# AAA_PowerSupply.net
KiCad netlist of a schematic drawn in EAGLE
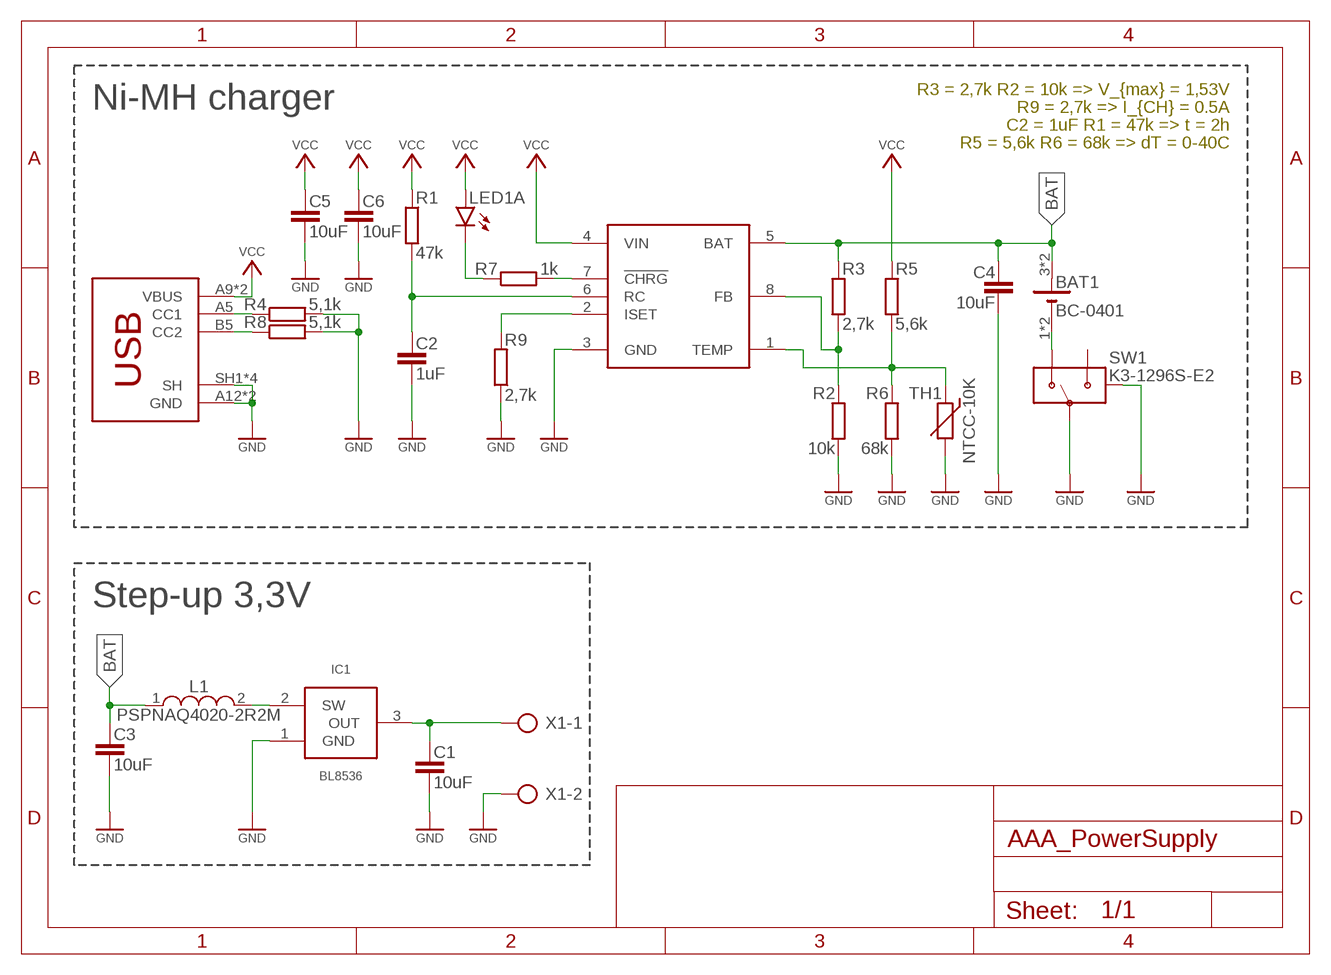
[diagram p0: schematic, sheet 1]

(export (version "E")
  (design (tool "Eeschema 10.0.6"))
  (components
    (comp (ref "BAT1")
      (value "BC-0401")
      (footprint "eagle-import:BC-0401")
      (libsource (lib "eagle-import") (part "BC-0401"))
    )
    (comp (ref "C1")
      (value "10uF")
      (footprint "eagle-import:C0805")
      (fields (field (name "SPICEPREFIX") "C"))
      (libsource (lib "eagle-import") (part "C-EUC0805"))
    )
    (comp (ref "C2")
      (value "1uF")
      (footprint "eagle-import:C0805")
      (fields (field (name "SPICEPREFIX") "C"))
      (libsource (lib "eagle-import") (part "C-EUC0805"))
    )
    (comp (ref "C3")
      (value "10uF")
      (footprint "eagle-import:C0805")
      (fields (field (name "SPICEPREFIX") "C"))
      (libsource (lib "eagle-import") (part "C-EUC0805"))
    )
    (comp (ref "C4")
      (value "10uF")
      (footprint "eagle-import:C0805")
      (fields (field (name "SPICEPREFIX") "C"))
      (libsource (lib "eagle-import") (part "C-EUC0805"))
    )
    (comp (ref "C5")
      (value "10uF")
      (footprint "eagle-import:C0805")
      (fields (field (name "SPICEPREFIX") "C"))
      (libsource (lib "eagle-import") (part "C-EUC0805"))
    )
    (comp (ref "C6")
      (value "10uF")
      (footprint "eagle-import:C0805")
      (fields (field (name "SPICEPREFIX") "C"))
      (libsource (lib "eagle-import") (part "C-EUC0805"))
    )
    (comp (ref "IC1")
      (value "BL8536")
      (footprint "eagle-import:SOT23")
      (libsource (lib "eagle-import") (part "BL8536"))
    )
    (comp (ref "IC2")
      (value "CN3085")
      (footprint "eagle-import:SOP8_THERMAL")
      (libsource (lib "eagle-import") (part "CN3085"))
    )
    (comp (ref "L1")
      (value "PSPNAQ4020-2R2M")
      (footprint "eagle-import:L-4X4")
      (libsource (lib "eagle-import") (part "INDUCTOR-4X4"))
    )
    (comp (ref "LED1")
      (value "LSG-T676")
      (footprint "eagle-import:WL-SFCW-0603")
      (libsource (lib "eagle-import") (part "LSG-T676"))
    )
    (comp (ref "R1")
      (value "47k")
      (footprint "eagle-import:R0805")
      (libsource (lib "eagle-import") (part "R-EU_R0805"))
    )
    (comp (ref "R2")
      (value "10k")
      (footprint "eagle-import:R0805")
      (libsource (lib "eagle-import") (part "R-EU_R0805"))
    )
    (comp (ref "R3")
      (value "2,7k")
      (footprint "eagle-import:R0805")
      (libsource (lib "eagle-import") (part "R-EU_R0805"))
    )
    (comp (ref "R4")
      (value "5,1k")
      (footprint "eagle-import:R0805")
      (libsource (lib "eagle-import") (part "R-EU_R0805"))
    )
    (comp (ref "R5")
      (value "5,6k")
      (footprint "eagle-import:R0805")
      (libsource (lib "eagle-import") (part "R-EU_R0805"))
    )
    (comp (ref "R6")
      (value "68k")
      (footprint "eagle-import:R0805")
      (libsource (lib "eagle-import") (part "R-EU_R0805"))
    )
    (comp (ref "R7")
      (value "1k")
      (footprint "eagle-import:R0805")
      (libsource (lib "eagle-import") (part "R-EU_R0805"))
    )
    (comp (ref "R8")
      (value "5,1k")
      (footprint "eagle-import:R0805")
      (libsource (lib "eagle-import") (part "R-EU_R0805"))
    )
    (comp (ref "R9")
      (value "2,7k")
      (footprint "eagle-import:R0805")
      (libsource (lib "eagle-import") (part "R-EU_R0805"))
    )
    (comp (ref "SW1")
      (value "K3-1296S-E2")
      (footprint "eagle-import:K3-1296S-E2")
      (libsource (lib "eagle-import") (part "K3-1296S-E2"))
    )
    (comp (ref "TH1")
      (value "NTCC-10K")
      (footprint "eagle-import:RS-2,5")
      (libsource (lib "eagle-import") (part "THERMISTOR-2,5"))
    )
    (comp (ref "X1")
      (value "AK500/2")
      (footprint "eagle-import:AK500_2")
      (libsource (lib "eagle-import") (part "AK500/2"))
    )
    (comp (ref "X2")
      (value "HC-TYPE-C-6P-01QT")
      (footprint "eagle-import:HC-TYPE-C-6P-01QT")
      (libsource (lib "eagle-import") (part "HC-TYPE-C-6P-01QT"))
    )
  )
  (nets
    (net (code "1") (name "BAT") (class "Default")
      (node (ref "BAT1") (pin "3") (pinfunction "+_3") (pintype "passive"))
      (node (ref "BAT1") (pin "4") (pinfunction "+_4") (pintype "passive"))
      (node (ref "C3") (pin "1") (pinfunction "1_1") (pintype "passive"))
      (node (ref "C4") (pin "1") (pinfunction "1_1") (pintype "passive"))
      (node (ref "IC2") (pin "5") (pinfunction "BAT_5") (pintype "bidirectional"))
      (node (ref "L1") (pin "1") (pinfunction "1_1") (pintype "passive"))
      (node (ref "R3") (pin "1") (pinfunction "1_1") (pintype "passive"))
    )
    (net (code "2") (name "GND") (class "Default")
      (node (ref "C1") (pin "2") (pinfunction "2_2") (pintype "passive"))
      (node (ref "C2") (pin "2") (pinfunction "2_2") (pintype "passive"))
      (node (ref "C3") (pin "2") (pinfunction "2_2") (pintype "passive"))
      (node (ref "C4") (pin "2") (pinfunction "2_2") (pintype "passive"))
      (node (ref "C5") (pin "2") (pinfunction "2_2") (pintype "passive"))
      (node (ref "C6") (pin "2") (pinfunction "2_2") (pintype "passive"))
      (node (ref "IC1") (pin "1") (pinfunction "GND_1") (pintype "bidirectional"))
      (node (ref "IC2") (pin "3") (pinfunction "GND_3") (pintype "bidirectional"))
      (node (ref "R2") (pin "2") (pinfunction "2_2") (pintype "passive"))
      (node (ref "R4") (pin "2") (pinfunction "2_2") (pintype "passive"))
      (node (ref "R6") (pin "2") (pinfunction "2_2") (pintype "passive"))
      (node (ref "R8") (pin "2") (pinfunction "2_2") (pintype "passive"))
      (node (ref "R9") (pin "1") (pinfunction "1_1") (pintype "passive"))
      (node (ref "SW1") (pin "P") (pinfunction "P_P") (pintype "passive"))
      (node (ref "SW1") (pin "SH1") (pinfunction "SH_SH1") (pintype "passive"))
      (node (ref "SW1") (pin "SH2") (pinfunction "SH_SH2") (pintype "passive"))
      (node (ref "SW1") (pin "SH3") (pinfunction "SH_SH3") (pintype "passive"))
      (node (ref "SW1") (pin "SH4") (pinfunction "SH_SH4") (pintype "passive"))
      (node (ref "TH1") (pin "2") (pinfunction "2_2") (pintype "passive"))
      (node (ref "X1") (pin "2") (pinfunction "KL_2") (pintype "passive"))
      (node (ref "X2") (pin "A12") (pinfunction "GND_A12") (pintype "bidirectional"))
      (node (ref "X2") (pin "B12") (pinfunction "GND_B12") (pintype "bidirectional"))
      (node (ref "X2") (pin "SH1") (pinfunction "SH_SH1") (pintype "bidirectional"))
      (node (ref "X2") (pin "SH2") (pinfunction "SH_SH2") (pintype "bidirectional"))
      (node (ref "X2") (pin "SH3") (pinfunction "SH_SH3") (pintype "bidirectional"))
      (node (ref "X2") (pin "SH4") (pinfunction "SH_SH4") (pintype "bidirectional"))
    )
    (net (code "3") (name "Net-(BAT1---Pad1)") (class "Default")
      (node (ref "BAT1") (pin "1") (pinfunction "-_1") (pintype "passive"))
      (node (ref "BAT1") (pin "2") (pinfunction "-_2") (pintype "passive"))
      (node (ref "SW1") (pin "O") (pinfunction "O_O") (pintype "passive"))
    )
    (net (code "4") (name "Net-(IC1-OUT)") (class "Default")
      (node (ref "C1") (pin "1") (pinfunction "1_1") (pintype "passive"))
      (node (ref "IC1") (pin "3") (pinfunction "OUT_3") (pintype "bidirectional"))
      (node (ref "X1") (pin "1") (pinfunction "KL_1") (pintype "passive"))
    )
    (net (code "5") (name "Net-(IC1-SW)") (class "Default")
      (node (ref "IC1") (pin "2") (pinfunction "SW_2") (pintype "bidirectional"))
      (node (ref "L1") (pin "2") (pinfunction "2_2") (pintype "passive"))
    )
    (net (code "6") (name "Net-(IC2-FB)") (class "Default")
      (node (ref "IC2") (pin "8") (pinfunction "FB_8") (pintype "bidirectional"))
      (node (ref "R2") (pin "1") (pinfunction "1_1") (pintype "passive"))
      (node (ref "R3") (pin "2") (pinfunction "2_2") (pintype "passive"))
    )
    (net (code "7") (name "Net-(IC2-ISET)") (class "Default")
      (node (ref "IC2") (pin "2") (pinfunction "ISET_2") (pintype "bidirectional"))
      (node (ref "R9") (pin "2") (pinfunction "2_2") (pintype "passive"))
    )
    (net (code "8") (name "Net-(IC2-RC)") (class "Default")
      (node (ref "C2") (pin "1") (pinfunction "1_1") (pintype "passive"))
      (node (ref "IC2") (pin "6") (pinfunction "RC_6") (pintype "bidirectional"))
      (node (ref "R1") (pin "2") (pinfunction "2_2") (pintype "passive"))
    )
    (net (code "9") (name "Net-(IC2-TEMP)") (class "Default")
      (node (ref "IC2") (pin "1") (pinfunction "TEMP_1") (pintype "bidirectional"))
      (node (ref "R5") (pin "2") (pinfunction "2_2") (pintype "passive"))
      (node (ref "R6") (pin "1") (pinfunction "1_1") (pintype "passive"))
      (node (ref "TH1") (pin "1") (pinfunction "1_1") (pintype "passive"))
    )
    (net (code "10") (name "Net-(IC2-~{CHRG})") (class "Default")
      (node (ref "IC2") (pin "7") (pinfunction "~{CHRG}_7") (pintype "bidirectional"))
      (node (ref "R7") (pin "2") (pinfunction "2_2") (pintype "passive"))
    )
    (net (code "11") (name "Net-(LED1A-C)") (class "Default")
      (node (ref "LED1") (pin "P$1") (pinfunction "C_P$1") (pintype "passive"))
      (node (ref "R7") (pin "1") (pinfunction "1_1") (pintype "passive"))
    )
    (net (code "12") (name "Net-(X2-CC1)") (class "Default")
      (node (ref "R4") (pin "1") (pinfunction "1_1") (pintype "passive"))
      (node (ref "X2") (pin "A5") (pinfunction "CC1_A5") (pintype "bidirectional"))
    )
    (net (code "13") (name "Net-(X2-CC2)") (class "Default")
      (node (ref "R8") (pin "1") (pinfunction "1_1") (pintype "passive"))
      (node (ref "X2") (pin "B5") (pinfunction "CC2_B5") (pintype "bidirectional"))
    )
    (net (code "14") (name "VCC") (class "Default")
      (node (ref "C5") (pin "1") (pinfunction "1_1") (pintype "passive"))
      (node (ref "C6") (pin "1") (pinfunction "1_1") (pintype "passive"))
      (node (ref "IC2") (pin "4") (pinfunction "VIN_4") (pintype "bidirectional"))
      (node (ref "LED1") (pin "P$2") (pinfunction "A_P$2") (pintype "passive"))
      (node (ref "R1") (pin "1") (pinfunction "1_1") (pintype "passive"))
      (node (ref "R5") (pin "1") (pinfunction "1_1") (pintype "passive"))
      (node (ref "X2") (pin "A9") (pinfunction "VBUS_A9") (pintype "bidirectional"))
      (node (ref "X2") (pin "B9") (pinfunction "VBUS_B9") (pintype "bidirectional"))
    )
    (net (code "15") (name "unconnected-(SW1-PadS)") (class "Default")
      (node (ref "SW1") (pin "S") (pinfunction "S_S") (pintype "passive"))
    )
  )
)
